# M1.net
KiCad netlist of a schematic drawn in Altium Designer
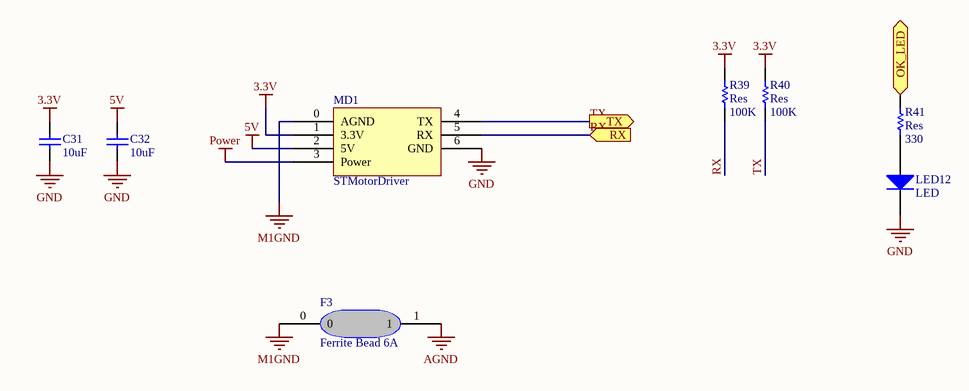
[diagram p0: M1.SchDoc]

(export (version "E")
  (design (tool "Eeschema 10.0.6"))
  (components
    (comp (ref "C31")
      (value "10uF")
      (footprint "2012[0805]")
      (description "Capacitor")
      (fields (field (name "Comment") "Cap_UP") (field (name "PUBLISHER") "Altium Limited"))
      (libsource (lib "KN2CLib") (part "Cap_UP"))
    )
    (comp (ref "C32")
      (value "10uF")
      (footprint "2012[0805]")
      (description "Capacitor")
      (fields (field (name "Comment") "Cap_UP") (field (name "PUBLISHER") "Altium Limited"))
      (libsource (lib "KN2CLib") (part "Cap_UP"))
    )
    (comp (ref "F3")
      (value "Ferrite Bead 6A")
      (footprint "f6A")
      (libsource (lib "Ferrite Bead") (part "F6A"))
    )
    (comp (ref "LED12")
      (value "LED")
      (footprint "2012[0805]")
      (description "1 Amp General Purpose Rectifier")
      (fields (field (name "PUBLISHER") "Altium Limited"))
      (libsource (lib "KN2CLib") (part "Diode"))
    )
    (comp (ref "MD1")
      (value "STMotorDriver")
      (footprint "MotorDriver")
      (libsource (lib "STMotorDriver") (part "STMotorDriver"))
    )
    (comp (ref "R39")
      (value "Res")
      (footprint "2012[0805]")
      (description "Semiconductor Resistor")
      (fields (field (name "ALTIUM_VALUE") "100K") (field (name "PUBLISHER") "Altium Limited"))
      (libsource (lib "KN2CLib") (part "Res"))
    )
    (comp (ref "R40")
      (value "Res")
      (footprint "2012[0805]")
      (description "Semiconductor Resistor")
      (fields (field (name "ALTIUM_VALUE") "100K") (field (name "PUBLISHER") "Altium Limited"))
      (libsource (lib "KN2CLib") (part "Res"))
    )
    (comp (ref "R41")
      (value "Res")
      (footprint "2012[0805]")
      (description "Semiconductor Resistor")
      (fields (field (name "ALTIUM_VALUE") "330") (field (name "PUBLISHER") "Altium Limited"))
      (libsource (lib "KN2CLib") (part "Res"))
    )
  )
  (nets
    (net (code "1") (name "/OK_LED") (class "Default")
      (node (ref "R41") (pin "1") (pinfunction "1_1") (pintype "passive"))
    )
    (net (code "2") (name "/RX") (class "Default")
      (node (ref "MD1") (pin "5") (pinfunction "RX_5") (pintype "passive"))
      (node (ref "R39") (pin "1") (pinfunction "1_1") (pintype "passive"))
    )
    (net (code "3") (name "/TX") (class "Default")
      (node (ref "MD1") (pin "4") (pinfunction "TX_4") (pintype "passive"))
      (node (ref "R40") (pin "1") (pinfunction "1_1") (pintype "passive"))
    )
    (net (code "4") (name "3.3V") (class "Default")
      (node (ref "C31") (pin "2") (pinfunction "2_2") (pintype "passive"))
      (node (ref "MD1") (pin "1") (pinfunction "3.3V_1") (pintype "passive"))
      (node (ref "R39") (pin "2") (pinfunction "2_2") (pintype "passive"))
      (node (ref "R40") (pin "2") (pinfunction "2_2") (pintype "passive"))
    )
    (net (code "5") (name "5V") (class "Default")
      (node (ref "C32") (pin "2") (pinfunction "2_2") (pintype "passive"))
      (node (ref "MD1") (pin "2") (pinfunction "5V_2") (pintype "passive"))
    )
    (net (code "6") (name "AGND") (class "Default")
      (node (ref "F3") (pin "1") (pinfunction "1_1") (pintype "passive"))
    )
    (net (code "7") (name "GND") (class "Default")
      (node (ref "C31") (pin "1") (pinfunction "1_1") (pintype "passive"))
      (node (ref "C32") (pin "1") (pinfunction "1_1") (pintype "passive"))
      (node (ref "LED12") (pin "2") (pinfunction "K_2") (pintype "passive"))
      (node (ref "MD1") (pin "6") (pinfunction "GND_6") (pintype "passive"))
    )
    (net (code "8") (name "M1GND") (class "Default")
      (node (ref "F3") (pin "0") (pinfunction "0_0") (pintype "passive"))
      (node (ref "MD1") (pin "0") (pinfunction "AGND_0") (pintype "passive"))
    )
    (net (code "9") (name "Net-(LED12-A)") (class "Default")
      (node (ref "LED12") (pin "1") (pinfunction "A_1") (pintype "passive"))
      (node (ref "R41") (pin "2") (pinfunction "2_2") (pintype "passive"))
    )
    (net (code "10") (name "Power") (class "Default")
      (node (ref "MD1") (pin "3") (pinfunction "Power_3") (pintype "passive"))
    )
  )
)
